# IRTHERMV2_1.net
KiCad netlist of a schematic drawn in EAGLE
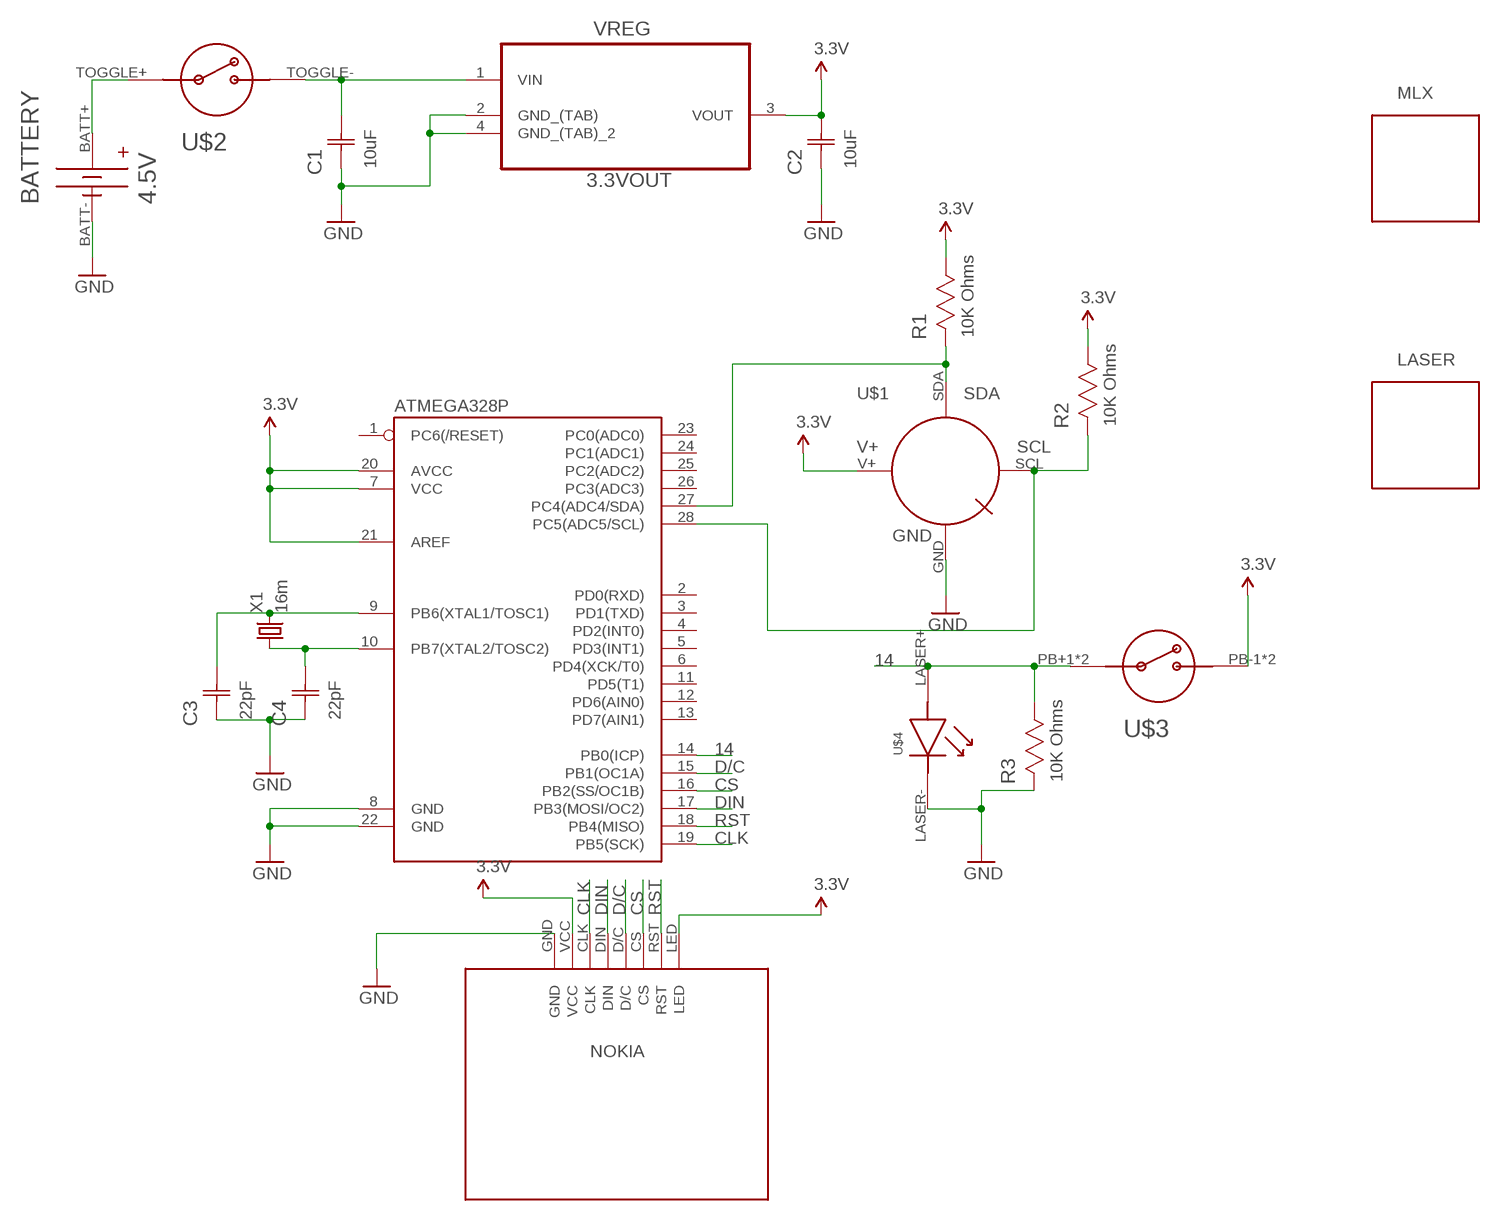
[diagram p0: schematic, sheet 1]

(export (version "E")
  (design (tool "Eeschema 10.0.6"))
  (components
    (comp (ref "ATMEGA328P")
      (value "ATMEGA328P_PDIP")
      (footprint "eagle-import:DIL28-3")
      (libsource (lib "eagle-import") (part "ATMEGA328P_PDIP"))
    )
    (comp (ref "BATTERY")
      (value "4.5V")
      (footprint "eagle-import:KEYSTONE2479")
      (libsource (lib "eagle-import") (part "KEYSTONE2479"))
    )
    (comp (ref "C1")
      (value "10uF")
      (footprint "eagle-import:CAPC3216X180N")
      (fields (field (name "MPN") "C1206C106K4RACTU") (field (name "TOLERANCE") "±10%"))
      (libsource (lib "eagle-import") (part "C1206C106K4RACTU"))
    )
    (comp (ref "C2")
      (value "10uF")
      (footprint "eagle-import:CAPC3216X180N")
      (fields (field (name "MPN") "C1206C106K4RACTU") (field (name "TOLERANCE") "±10%"))
      (libsource (lib "eagle-import") (part "C1206C106K4RACTU"))
    )
    (comp (ref "C3")
      (value "22pF")
      (footprint "eagle-import:CAPC3216X88N")
      (fields (field (name "MPN") "C1206C220J5GACTU") (field (name "TOLERANCE") "±5%"))
      (libsource (lib "eagle-import") (part "C1206C220J5GACTU"))
    )
    (comp (ref "C4")
      (value "22pF")
      (footprint "eagle-import:CAPC3216X88N")
      (fields (field (name "MPN") "C1206C220J5GACTU") (field (name "TOLERANCE") "±5%"))
      (libsource (lib "eagle-import") (part "C1206C220J5GACTU"))
    )
    (comp (ref "LASER")
      (value "KEYSTONECLIP")
      (footprint "eagle-import:KEYSTONE50")
      (libsource (lib "eagle-import") (part "KEYSTONECLIP"))
    )
    (comp (ref "MLX")
      (value "KEYSTONECLIP")
      (footprint "eagle-import:KEYSTONE50")
      (libsource (lib "eagle-import") (part "KEYSTONECLIP"))
    )
    (comp (ref "R1")
      (value "10K Ohms")
      (footprint "eagle-import:RESC3216X71N")
      (fields (field (name "MPN") "CRCW120610K0JNEA") (field (name "TOLERANCE") "±5%"))
      (libsource (lib "eagle-import") (part "CRCW120610K0JNEA"))
    )
    (comp (ref "R2")
      (value "10K Ohms")
      (footprint "eagle-import:RESC3216X71N")
      (fields (field (name "MPN") "CRCW120610K0JNEA") (field (name "TOLERANCE") "±5%"))
      (libsource (lib "eagle-import") (part "CRCW120610K0JNEA"))
    )
    (comp (ref "R3")
      (value "10K Ohms")
      (footprint "eagle-import:RESC3216X71N")
      (fields (field (name "MPN") "CRCW120610K0JNEA") (field (name "TOLERANCE") "±5%"))
      (libsource (lib "eagle-import") (part "CRCW120610K0JNEA"))
    )
    (comp (ref "U$1")
      (value "MLX90614")
      (footprint "eagle-import:MLX90614")
      (libsource (lib "eagle-import") (part "MLX90614"))
    )
    (comp (ref "U$2")
      (value "1683ON-OFFTOGGLE")
      (footprint "eagle-import:1683ON-OFFTOGGLE")
      (libsource (lib "eagle-import") (part "1683ON-OFFTOGGLE"))
    )
    (comp (ref "U$3")
      (value "1009PUSHBUTTON")
      (footprint "eagle-import:1009PUSHBUTTON")
      (libsource (lib "eagle-import") (part "1009PUSHBUTTON"))
    )
    (comp (ref "U$4")
      (value "LASER")
      (footprint "eagle-import:LASER")
      (libsource (lib "eagle-import") (part "LASER"))
    )
    (comp (ref "U$5")
      (value "NOKIA")
      (footprint "eagle-import:NOKIA")
      (libsource (lib "eagle-import") (part "NOKIA"))
    )
    (comp (ref "VREG")
      (value "3.3VOUT")
      (footprint "eagle-import:SOT230P700X180-4N")
      (fields (field (name "MPN") "MCP1824ST-3302E/DB"))
      (libsource (lib "eagle-import") (part "MCP1824ST-3302E/DB"))
    )
    (comp (ref "X1")
      (value "16m")
      (footprint "eagle-import:HC49US")
      (libsource (lib "eagle-import") (part "CRYSTALHC49US"))
    )
  )
  (nets
    (net (code "1") (name "/14") (class "Default")
      (node (ref "ATMEGA328P") (pin "14") (pinfunction "PB0(ICP)_14") (pintype "bidirectional"))
      (node (ref "R3") (pin "1") (pinfunction "1_1") (pintype "passive"))
      (node (ref "U$3") (pin "PB+1") (pinfunction "ONOFF+_PB+1") (pintype "bidirectional"))
      (node (ref "U$3") (pin "PB+2") (pinfunction "ONOFF+_PB+2") (pintype "bidirectional"))
      (node (ref "U$4") (pin "LASER+") (pinfunction "LASER+_LASER+") (pintype "bidirectional"))
    )
    (net (code "2") (name "/CLK") (class "Default")
      (node (ref "ATMEGA328P") (pin "19") (pinfunction "PB5(SCK)_19") (pintype "bidirectional"))
      (node (ref "U$5") (pin "CLK") (pinfunction "CLK_CLK") (pintype "bidirectional"))
    )
    (net (code "3") (name "/CS") (class "Default")
      (node (ref "ATMEGA328P") (pin "16") (pinfunction "PB2(SS/OC1B)_16") (pintype "bidirectional"))
      (node (ref "U$5") (pin "CS") (pinfunction "CS_CS") (pintype "bidirectional"))
    )
    (net (code "4") (name "/DIN") (class "Default")
      (node (ref "ATMEGA328P") (pin "17") (pinfunction "PB3(MOSI/OC2)_17") (pintype "bidirectional"))
      (node (ref "U$5") (pin "DIN") (pinfunction "DIN_DIN") (pintype "bidirectional"))
    )
    (net (code "5") (name "/D{slash}C") (class "Default")
      (node (ref "ATMEGA328P") (pin "15") (pinfunction "PB1(OC1A)_15") (pintype "bidirectional"))
      (node (ref "U$5") (pin "D/C") (pinfunction "D/C_D/C") (pintype "bidirectional"))
    )
    (net (code "6") (name "/RST") (class "Default")
      (node (ref "ATMEGA328P") (pin "18") (pinfunction "PB4(MISO)_18") (pintype "bidirectional"))
      (node (ref "U$5") (pin "RST") (pinfunction "RST_RST") (pintype "bidirectional"))
    )
    (net (code "7") (name "3.3V") (class "Default")
      (node (ref "ATMEGA328P") (pin "20") (pinfunction "AVCC_20") (pintype "bidirectional"))
      (node (ref "ATMEGA328P") (pin "21") (pinfunction "AREF_21") (pintype "bidirectional"))
      (node (ref "ATMEGA328P") (pin "7") (pinfunction "VCC_7") (pintype "bidirectional"))
      (node (ref "C2") (pin "2") (pinfunction "C2_2") (pintype "passive"))
      (node (ref "R1") (pin "1") (pinfunction "1_1") (pintype "passive"))
      (node (ref "R2") (pin "1") (pinfunction "1_1") (pintype "passive"))
      (node (ref "U$1") (pin "V+") (pinfunction "MLXV+_V+") (pintype "bidirectional"))
      (node (ref "U$3") (pin "PB-1") (pinfunction "ONOFF-_PB-1") (pintype "bidirectional"))
      (node (ref "U$3") (pin "PB-2") (pinfunction "ONOFF-_PB-2") (pintype "bidirectional"))
      (node (ref "U$5") (pin "LED") (pinfunction "LED_LED") (pintype "bidirectional"))
      (node (ref "U$5") (pin "VCC") (pinfunction "VCC_VCC") (pintype "bidirectional"))
      (node (ref "VREG") (pin "3") (pinfunction "VOUT_3") (pintype "output"))
    )
    (net (code "8") (name "GND") (class "Default")
      (node (ref "ATMEGA328P") (pin "22") (pinfunction "GND_22") (pintype "bidirectional"))
      (node (ref "ATMEGA328P") (pin "8") (pinfunction "GND_8") (pintype "bidirectional"))
      (node (ref "BATTERY") (pin "BATT-") (pinfunction "BATT-_BATT-") (pintype "bidirectional"))
      (node (ref "C1") (pin "1") (pinfunction "C1_1") (pintype "passive"))
      (node (ref "C2") (pin "1") (pinfunction "C1_1") (pintype "passive"))
      (node (ref "C3") (pin "1") (pinfunction "C1_1") (pintype "passive"))
      (node (ref "C4") (pin "1") (pinfunction "C1_1") (pintype "passive"))
      (node (ref "R3") (pin "2") (pinfunction "2_2") (pintype "passive"))
      (node (ref "U$1") (pin "GND") (pinfunction "MLXGND_GND") (pintype "bidirectional"))
      (node (ref "U$4") (pin "LASER-") (pinfunction "LASERGND_LASER-") (pintype "bidirectional"))
      (node (ref "U$5") (pin "GND") (pinfunction "GND_GND") (pintype "bidirectional"))
      (node (ref "VREG") (pin "2") (pinfunction "GND_(TAB)_2") (pintype "passive"))
      (node (ref "VREG") (pin "4") (pinfunction "GND_(TAB)_2_4") (pintype "passive"))
    )
    (net (code "9") (name "Net-(ATMEGA328P-PB6(XTAL1{slash}TOSC1))") (class "Default")
      (node (ref "ATMEGA328P") (pin "9") (pinfunction "PB6(XTAL1/TOSC1)_9") (pintype "bidirectional"))
      (node (ref "C3") (pin "2") (pinfunction "C2_2") (pintype "passive"))
      (node (ref "X1") (pin "2") (pinfunction "2_2") (pintype "passive"))
    )
    (net (code "10") (name "Net-(ATMEGA328P-PB7(XTAL2{slash}TOSC2))") (class "Default")
      (node (ref "ATMEGA328P") (pin "10") (pinfunction "PB7(XTAL2/TOSC2)_10") (pintype "bidirectional"))
      (node (ref "C4") (pin "2") (pinfunction "C2_2") (pintype "passive"))
      (node (ref "X1") (pin "1") (pinfunction "1_1") (pintype "passive"))
    )
    (net (code "11") (name "Net-(ATMEGA328P-PC4(ADC4{slash}SDA))") (class "Default")
      (node (ref "ATMEGA328P") (pin "27") (pinfunction "PC4(ADC4/SDA)_27") (pintype "bidirectional"))
      (node (ref "R1") (pin "2") (pinfunction "2_2") (pintype "passive"))
      (node (ref "U$1") (pin "SDA") (pinfunction "MLXSDA_SDA") (pintype "bidirectional"))
    )
    (net (code "12") (name "Net-(ATMEGA328P-PC5(ADC5{slash}SCL))") (class "Default")
      (node (ref "ATMEGA328P") (pin "28") (pinfunction "PC5(ADC5/SCL)_28") (pintype "bidirectional"))
      (node (ref "R2") (pin "2") (pinfunction "2_2") (pintype "passive"))
      (node (ref "U$1") (pin "SCL") (pinfunction "MLXSCL_SCL") (pintype "bidirectional"))
    )
    (net (code "13") (name "Net-(C1-C2)") (class "Default")
      (node (ref "C1") (pin "2") (pinfunction "C2_2") (pintype "passive"))
      (node (ref "U$2") (pin "TOGGLE-") (pinfunction "ONOFF-_TOGGLE-") (pintype "bidirectional"))
      (node (ref "VREG") (pin "1") (pinfunction "VIN_1") (pintype "input"))
    )
    (net (code "14") (name "Net-(U$2-ONOFF+)") (class "Default")
      (node (ref "BATTERY") (pin "BATT+") (pinfunction "BATT+_BATT+") (pintype "bidirectional"))
      (node (ref "U$2") (pin "TOGGLE+") (pinfunction "ONOFF+_TOGGLE+") (pintype "bidirectional"))
    )
    (net (code "15") (name "unconnected-(ATMEGA328P-PC0(ADC0)-Pad23)") (class "Default")
      (node (ref "ATMEGA328P") (pin "23") (pinfunction "PC0(ADC0)_23") (pintype "bidirectional"))
    )
    (net (code "16") (name "unconnected-(ATMEGA328P-PC1(ADC1)-Pad24)") (class "Default")
      (node (ref "ATMEGA328P") (pin "24") (pinfunction "PC1(ADC1)_24") (pintype "bidirectional"))
    )
    (net (code "17") (name "unconnected-(ATMEGA328P-PC2(ADC2)-Pad25)") (class "Default")
      (node (ref "ATMEGA328P") (pin "25") (pinfunction "PC2(ADC2)_25") (pintype "bidirectional"))
    )
    (net (code "18") (name "unconnected-(ATMEGA328P-PC3(ADC3)-Pad26)") (class "Default")
      (node (ref "ATMEGA328P") (pin "26") (pinfunction "PC3(ADC3)_26") (pintype "bidirectional"))
    )
    (net (code "19") (name "unconnected-(ATMEGA328P-PC6({slash}RESET)-Pad1)") (class "Default")
      (node (ref "ATMEGA328P") (pin "1") (pinfunction "PC6(/RESET)_1") (pintype "bidirectional"))
    )
    (net (code "20") (name "unconnected-(ATMEGA328P-PD0(RXD)-Pad2)") (class "Default")
      (node (ref "ATMEGA328P") (pin "2") (pinfunction "PD0(RXD)_2") (pintype "bidirectional"))
    )
    (net (code "21") (name "unconnected-(ATMEGA328P-PD1(TXD)-Pad3)") (class "Default")
      (node (ref "ATMEGA328P") (pin "3") (pinfunction "PD1(TXD)_3") (pintype "bidirectional"))
    )
    (net (code "22") (name "unconnected-(ATMEGA328P-PD2(INT0)-Pad4)") (class "Default")
      (node (ref "ATMEGA328P") (pin "4") (pinfunction "PD2(INT0)_4") (pintype "bidirectional"))
    )
    (net (code "23") (name "unconnected-(ATMEGA328P-PD3(INT1)-Pad5)") (class "Default")
      (node (ref "ATMEGA328P") (pin "5") (pinfunction "PD3(INT1)_5") (pintype "bidirectional"))
    )
    (net (code "24") (name "unconnected-(ATMEGA328P-PD4(XCK{slash}T0)-Pad6)") (class "Default")
      (node (ref "ATMEGA328P") (pin "6") (pinfunction "PD4(XCK/T0)_6") (pintype "bidirectional"))
    )
    (net (code "25") (name "unconnected-(ATMEGA328P-PD5(T1)-Pad11)") (class "Default")
      (node (ref "ATMEGA328P") (pin "11") (pinfunction "PD5(T1)_11") (pintype "bidirectional"))
    )
    (net (code "26") (name "unconnected-(ATMEGA328P-PD6(AIN0)-Pad12)") (class "Default")
      (node (ref "ATMEGA328P") (pin "12") (pinfunction "PD6(AIN0)_12") (pintype "bidirectional"))
    )
    (net (code "27") (name "unconnected-(ATMEGA328P-PD7(AIN1)-Pad13)") (class "Default")
      (node (ref "ATMEGA328P") (pin "13") (pinfunction "PD7(AIN1)_13") (pintype "bidirectional"))
    )
  )
)
